# GarderOpa.net
KiCad netlist of a schematic drawn in EAGLE
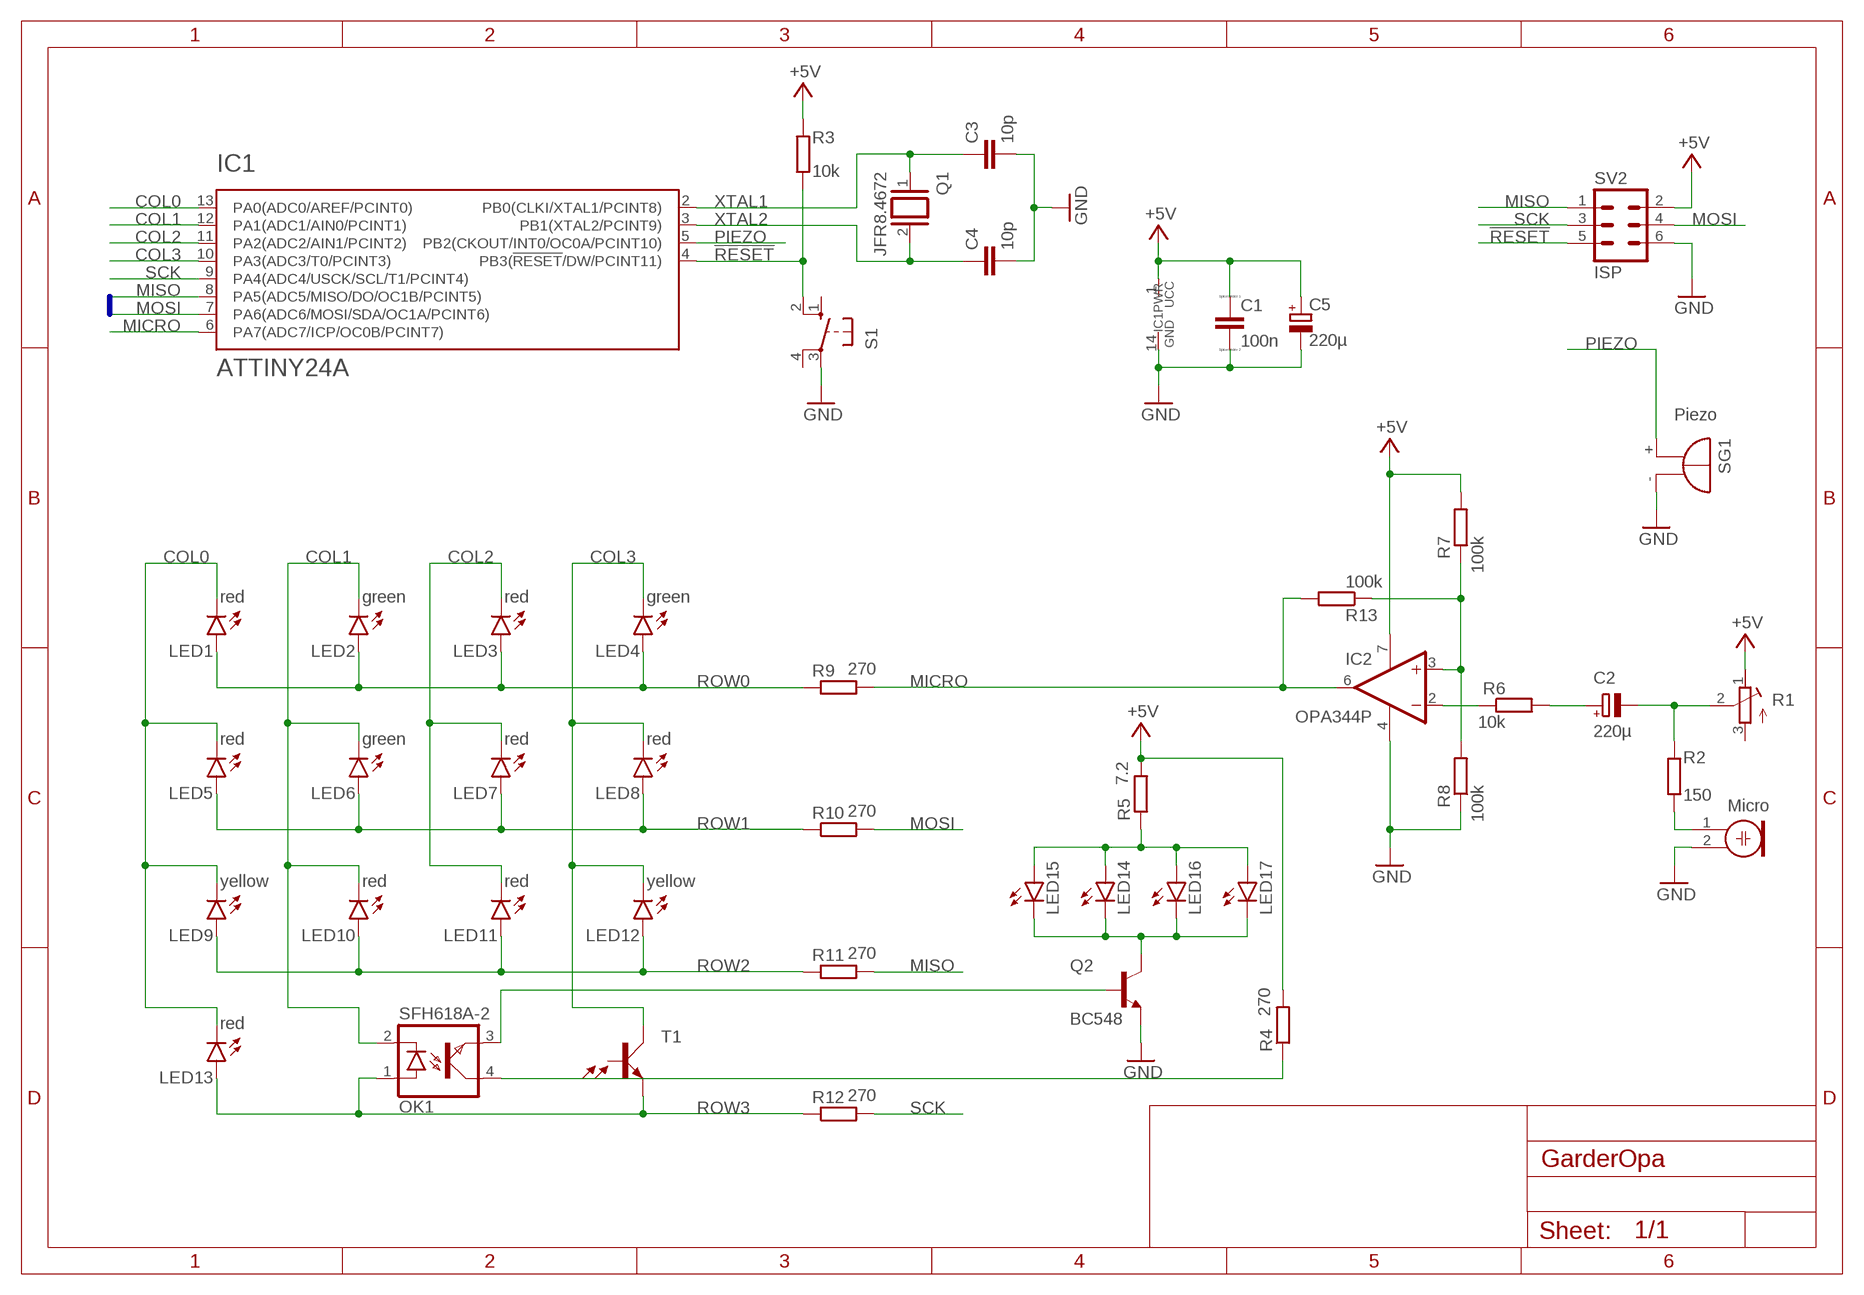
[diagram p0: schematic, sheet 1]

(export (version "E")
  (design (tool "Eeschema 10.0.6"))
  (components
    (comp (ref "C1")
      (value "100n")
      (footprint "eagle-import:C0603")
      (libsource (lib "eagle-import") (part "CC0603"))
    )
    (comp (ref "C2")
      (value "220µ")
      (footprint "eagle-import:E2-4")
      (libsource (lib "eagle-import") (part "CPOL-EUE2-4"))
    )
    (comp (ref "C3")
      (value "10p")
      (footprint "eagle-import:C025-024X044")
      (libsource (lib "eagle-import") (part "C-EU025-024X044"))
    )
    (comp (ref "C4")
      (value "10p")
      (footprint "eagle-import:C025-024X044")
      (libsource (lib "eagle-import") (part "C-EU025-024X044"))
    )
    (comp (ref "C5")
      (value "220µ")
      (footprint "eagle-import:E2-4")
      (libsource (lib "eagle-import") (part "CPOL-EUE2-4"))
    )
    (comp (ref "IC1")
      (value "ATTINY24A")
      (footprint "eagle-import:DIL14")
      (libsource (lib "eagle-import") (part "ATTINY24/44/84-PU"))
    )
    (comp (ref "IC2")
      (value "OPA344P")
      (footprint "eagle-import:DIL08")
      (libsource (lib "eagle-import") (part "OPAP344"))
    )
    (comp (ref "LED1")
      (value "red")
      (footprint "eagle-import:LED3MM")
      (libsource (lib "eagle-import") (part "LED3MM"))
    )
    (comp (ref "LED2")
      (value "green")
      (footprint "eagle-import:LED3MM")
      (libsource (lib "eagle-import") (part "LED3MM"))
    )
    (comp (ref "LED3")
      (value "red")
      (footprint "eagle-import:LED3MM")
      (libsource (lib "eagle-import") (part "LED3MM"))
    )
    (comp (ref "LED4")
      (value "green")
      (footprint "eagle-import:LED3MM")
      (libsource (lib "eagle-import") (part "LED3MM"))
    )
    (comp (ref "LED5")
      (value "red")
      (footprint "eagle-import:LED3MM")
      (libsource (lib "eagle-import") (part "LED3MM"))
    )
    (comp (ref "LED6")
      (value "green")
      (footprint "eagle-import:LED3MM")
      (libsource (lib "eagle-import") (part "LED3MM"))
    )
    (comp (ref "LED7")
      (value "red")
      (footprint "eagle-import:LED3MM")
      (libsource (lib "eagle-import") (part "LED3MM"))
    )
    (comp (ref "LED8")
      (value "red")
      (footprint "eagle-import:LED3MM")
      (libsource (lib "eagle-import") (part "LED3MM"))
    )
    (comp (ref "LED9")
      (value "yellow")
      (footprint "eagle-import:LED3MM")
      (libsource (lib "eagle-import") (part "LED3MM"))
    )
    (comp (ref "LED10")
      (value "red")
      (footprint "eagle-import:LED3MM")
      (libsource (lib "eagle-import") (part "LED3MM"))
    )
    (comp (ref "LED11")
      (value "red")
      (footprint "eagle-import:LED3MM")
      (libsource (lib "eagle-import") (part "LED3MM"))
    )
    (comp (ref "LED12")
      (value "yellow")
      (footprint "eagle-import:LED3MM")
      (libsource (lib "eagle-import") (part "LED3MM"))
    )
    (comp (ref "LED13")
      (value "red")
      (footprint "eagle-import:LED3MM")
      (libsource (lib "eagle-import") (part "LED3MM"))
    )
    (comp (ref "LED14")
      (value "LED5MM")
      (footprint "eagle-import:LED5MM")
      (libsource (lib "eagle-import") (part "LED5MM"))
    )
    (comp (ref "LED15")
      (value "LED5MM")
      (footprint "eagle-import:LED5MM")
      (libsource (lib "eagle-import") (part "LED5MM"))
    )
    (comp (ref "LED16")
      (value "LED5MM")
      (footprint "eagle-import:LED5MM")
      (libsource (lib "eagle-import") (part "LED5MM"))
    )
    (comp (ref "LED17")
      (value "LED5MM")
      (footprint "eagle-import:LED5MM")
      (libsource (lib "eagle-import") (part "LED5MM"))
    )
    (comp (ref "M1")
      (value "Micro")
      (footprint "eagle-import:WM-61B")
      (fields (field (name "MIC") "Micro"))
      (libsource (lib "eagle-import") (part "ELECTRET_MICROPHON-WM-61B"))
    )
    (comp (ref "OK1")
      (value "SFH618A-2")
      (footprint "eagle-import:DIP4")
      (fields (field (name "MF") "VISHAY/TELEFUNKEN"))
      (libsource (lib "eagle-import") (part "SFH618?A-2"))
    )
    (comp (ref "Q1")
      (value "JFR8.4672")
      (footprint "eagle-import:QS")
      (libsource (lib "eagle-import") (part "XTAL/S"))
    )
    (comp (ref "Q2")
      (value "BC548")
      (footprint "eagle-import:TO92-EBC")
      (libsource (lib "eagle-import") (part "BC548"))
    )
    (comp (ref "R1")
      (value "R-TRIMM43P")
      (footprint "eagle-import:RTRIM43P")
      (libsource (lib "eagle-import") (part "R-TRIMM43P"))
    )
    (comp (ref "R2")
      (value "150")
      (footprint "eagle-import:0204_7")
      (libsource (lib "eagle-import") (part "rcl_334_R-EU_0204/7"))
    )
    (comp (ref "R3")
      (value "10k")
      (footprint "eagle-import:R0603")
      (libsource (lib "eagle-import") (part "R-EU_R0603"))
    )
    (comp (ref "R4")
      (value "270")
      (footprint "eagle-import:R0603")
      (libsource (lib "eagle-import") (part "R-EU_R0603"))
    )
    (comp (ref "R5")
      (value "7.2")
      (footprint "eagle-import:R0603")
      (libsource (lib "eagle-import") (part "R-EU_R0603"))
    )
    (comp (ref "R6")
      (value "10k")
      (footprint "eagle-import:0204_7")
      (libsource (lib "eagle-import") (part "rcl_334_R-EU_0204/7"))
    )
    (comp (ref "R7")
      (value "100k")
      (footprint "eagle-import:0204_7")
      (libsource (lib "eagle-import") (part "rcl_334_R-EU_0204/7"))
    )
    (comp (ref "R8")
      (value "100k")
      (footprint "eagle-import:0204_7")
      (libsource (lib "eagle-import") (part "rcl_334_R-EU_0204/7"))
    )
    (comp (ref "R9")
      (value "270")
      (footprint "eagle-import:R0603")
      (libsource (lib "eagle-import") (part "R-EU_R0603"))
    )
    (comp (ref "R10")
      (value "270")
      (footprint "eagle-import:R0603")
      (libsource (lib "eagle-import") (part "R-EU_R0603"))
    )
    (comp (ref "R11")
      (value "270")
      (footprint "eagle-import:R0603")
      (libsource (lib "eagle-import") (part "R-EU_R0603"))
    )
    (comp (ref "R12")
      (value "270")
      (footprint "eagle-import:R0603")
      (libsource (lib "eagle-import") (part "R-EU_R0603"))
    )
    (comp (ref "R13")
      (value "100k")
      (footprint "eagle-import:0204_7")
      (libsource (lib "eagle-import") (part "rcl_334_R-EU_0204/7"))
    )
    (comp (ref "S1")
      (value "10-XX")
      (footprint "eagle-import:B3F-10XX")
      (fields (field (name "MPN") "B3F-1000"))
      (libsource (lib "eagle-import") (part "10-XX"))
    )
    (comp (ref "SG1")
      (value "Piezo")
      (footprint "eagle-import:EB2505")
      (libsource (lib "eagle-import") (part "EB2505"))
    )
    (comp (ref "SV2")
      (value "ISP")
      (footprint "eagle-import:MA03-2")
      (libsource (lib "eagle-import") (part "MA03-2"))
    )
    (comp (ref "T1")
      (value "SFH303")
      (footprint "eagle-import:SFH303")
      (libsource (lib "eagle-import") (part "SFH303"))
    )
  )
  (nets
    (net (code "1") (name "+5V") (class "Default")
      (node (ref "C1") (pin "1") (pinfunction "1_1") (pintype "passive"))
      (node (ref "C5") (pin "+") (pinfunction "+_+") (pintype "passive"))
      (node (ref "IC1") (pin "1") (pinfunction "UCC_1") (pintype "power_in"))
      (node (ref "IC2") (pin "7") (pinfunction "V+_7") (pintype "power_in"))
      (node (ref "R1") (pin "1") (pinfunction "E_1") (pintype "passive"))
      (node (ref "R3") (pin "2") (pinfunction "2_2") (pintype "passive"))
      (node (ref "R4") (pin "2") (pinfunction "2_2") (pintype "passive"))
      (node (ref "R5") (pin "2") (pinfunction "2_2") (pintype "passive"))
      (node (ref "R7") (pin "2") (pinfunction "2_2") (pintype "passive"))
      (node (ref "SV2") (pin "2") (pinfunction "2_2") (pintype "passive"))
    )
    (net (code "2") (name "/COL0") (class "Default")
      (node (ref "IC1") (pin "13") (pinfunction "PA0(ADC0/AREF/PCINT0)_13") (pintype "bidirectional"))
      (node (ref "LED1") (pin "K") (pinfunction "C_K") (pintype "passive"))
      (node (ref "LED13") (pin "K") (pinfunction "C_K") (pintype "passive"))
      (node (ref "LED5") (pin "K") (pinfunction "C_K") (pintype "passive"))
      (node (ref "LED9") (pin "K") (pinfunction "C_K") (pintype "passive"))
    )
    (net (code "3") (name "/COL1") (class "Default")
      (node (ref "IC1") (pin "12") (pinfunction "PA1(ADC1/AIN0/PCINT1)_12") (pintype "bidirectional"))
      (node (ref "LED10") (pin "K") (pinfunction "C_K") (pintype "passive"))
      (node (ref "LED2") (pin "K") (pinfunction "C_K") (pintype "passive"))
      (node (ref "LED6") (pin "K") (pinfunction "C_K") (pintype "passive"))
      (node (ref "OK1") (pin "2") (pinfunction "C_2") (pintype "passive"))
    )
    (net (code "4") (name "/COL2") (class "Default")
      (node (ref "IC1") (pin "11") (pinfunction "PA2(ADC2/AIN1/PCINT2)_11") (pintype "bidirectional"))
      (node (ref "LED11") (pin "K") (pinfunction "C_K") (pintype "passive"))
      (node (ref "LED3") (pin "K") (pinfunction "C_K") (pintype "passive"))
      (node (ref "LED7") (pin "K") (pinfunction "C_K") (pintype "passive"))
    )
    (net (code "5") (name "/COL3") (class "Default")
      (node (ref "IC1") (pin "10") (pinfunction "PA3(ADC3/T0/PCINT3)_10") (pintype "bidirectional"))
      (node (ref "LED12") (pin "K") (pinfunction "C_K") (pintype "passive"))
      (node (ref "LED4") (pin "K") (pinfunction "C_K") (pintype "passive"))
      (node (ref "LED8") (pin "K") (pinfunction "C_K") (pintype "passive"))
      (node (ref "T1") (pin "2") (pinfunction "C_2") (pintype "passive"))
    )
    (net (code "6") (name "/MICRO") (class "Default")
      (node (ref "IC1") (pin "6") (pinfunction "PA7(ADC7/ICP/OC0B/PCINT7)_6") (pintype "bidirectional"))
      (node (ref "IC2") (pin "6") (pinfunction "OUT_6") (pintype "output"))
      (node (ref "R13") (pin "2") (pinfunction "2_2") (pintype "passive"))
      (node (ref "R9") (pin "2") (pinfunction "2_2") (pintype "passive"))
    )
    (net (code "7") (name "/MISO") (class "Default")
      (node (ref "IC1") (pin "8") (pinfunction "PA5(ADC5/MISO/DO/OC1B/PCINT5)_8") (pintype "bidirectional"))
      (node (ref "R11") (pin "2") (pinfunction "2_2") (pintype "passive"))
      (node (ref "SV2") (pin "1") (pinfunction "1_1") (pintype "passive"))
    )
    (net (code "8") (name "/MOSI") (class "Default")
      (node (ref "IC1") (pin "7") (pinfunction "PA6(ADC6/MOSI/SDA/OC1A/PCINT6)_7") (pintype "bidirectional"))
      (node (ref "R10") (pin "2") (pinfunction "2_2") (pintype "passive"))
      (node (ref "SV2") (pin "4") (pinfunction "4_4") (pintype "passive"))
    )
    (net (code "9") (name "/PIEZO") (class "Default")
      (node (ref "IC1") (pin "5") (pinfunction "PB2(CKOUT/INT0/OC0A/PCINT10)_5") (pintype "bidirectional"))
      (node (ref "SG1") (pin "+") (pinfunction "+_+") (pintype "passive"))
    )
    (net (code "10") (name "/ROW0") (class "Default")
      (node (ref "LED1") (pin "A") (pinfunction "A_A") (pintype "passive"))
      (node (ref "LED2") (pin "A") (pinfunction "A_A") (pintype "passive"))
      (node (ref "LED3") (pin "A") (pinfunction "A_A") (pintype "passive"))
      (node (ref "LED4") (pin "A") (pinfunction "A_A") (pintype "passive"))
      (node (ref "R9") (pin "1") (pinfunction "1_1") (pintype "passive"))
    )
    (net (code "11") (name "/ROW1") (class "Default")
      (node (ref "LED5") (pin "A") (pinfunction "A_A") (pintype "passive"))
      (node (ref "LED6") (pin "A") (pinfunction "A_A") (pintype "passive"))
      (node (ref "LED7") (pin "A") (pinfunction "A_A") (pintype "passive"))
      (node (ref "LED8") (pin "A") (pinfunction "A_A") (pintype "passive"))
      (node (ref "R10") (pin "1") (pinfunction "1_1") (pintype "passive"))
    )
    (net (code "12") (name "/ROW2") (class "Default")
      (node (ref "LED10") (pin "A") (pinfunction "A_A") (pintype "passive"))
      (node (ref "LED11") (pin "A") (pinfunction "A_A") (pintype "passive"))
      (node (ref "LED12") (pin "A") (pinfunction "A_A") (pintype "passive"))
      (node (ref "LED9") (pin "A") (pinfunction "A_A") (pintype "passive"))
      (node (ref "R11") (pin "1") (pinfunction "1_1") (pintype "passive"))
    )
    (net (code "13") (name "/ROW3") (class "Default")
      (node (ref "LED13") (pin "A") (pinfunction "A_A") (pintype "passive"))
      (node (ref "OK1") (pin "1") (pinfunction "A_1") (pintype "passive"))
      (node (ref "R12") (pin "1") (pinfunction "1_1") (pintype "passive"))
      (node (ref "T1") (pin "1") (pinfunction "E_1") (pintype "passive"))
    )
    (net (code "14") (name "/SCK") (class "Default")
      (node (ref "IC1") (pin "9") (pinfunction "PA4(ADC4/USCK/SCL/T1/PCINT4)_9") (pintype "bidirectional"))
      (node (ref "R12") (pin "2") (pinfunction "2_2") (pintype "passive"))
      (node (ref "SV2") (pin "3") (pinfunction "3_3") (pintype "passive"))
    )
    (net (code "15") (name "/XTAL1") (class "Default")
      (node (ref "C3") (pin "1") (pinfunction "1_1") (pintype "passive"))
      (node (ref "IC1") (pin "2") (pinfunction "PB0(CLKI/XTAL1/PCINT8)_2") (pintype "bidirectional"))
      (node (ref "Q1") (pin "1") (pinfunction "1_1") (pintype "passive"))
    )
    (net (code "16") (name "/XTAL2") (class "Default")
      (node (ref "C4") (pin "1") (pinfunction "1_1") (pintype "passive"))
      (node (ref "IC1") (pin "3") (pinfunction "PB1(XTAL2/PCINT9)_3") (pintype "bidirectional"))
      (node (ref "Q1") (pin "2") (pinfunction "2_2") (pintype "passive"))
    )
    (net (code "17") (name "/~{RESET}") (class "Default")
      (node (ref "IC1") (pin "4") (pinfunction "PB3(~{RESET}/DW/PCINT11)_4") (pintype "bidirectional"))
      (node (ref "R3") (pin "1") (pinfunction "1_1") (pintype "passive"))
      (node (ref "S1") (pin "2") (pinfunction "S1_2") (pintype "passive"))
      (node (ref "SV2") (pin "5") (pinfunction "5_5") (pintype "passive"))
    )
    (net (code "18") (name "GND") (class "Default")
      (node (ref "C1") (pin "2") (pinfunction "2_2") (pintype "passive"))
      (node (ref "C3") (pin "2") (pinfunction "2_2") (pintype "passive"))
      (node (ref "C4") (pin "2") (pinfunction "2_2") (pintype "passive"))
      (node (ref "C5") (pin "-") (pinfunction "-_-") (pintype "passive"))
      (node (ref "IC1") (pin "14") (pinfunction "GND_14") (pintype "power_in"))
      (node (ref "IC2") (pin "4") (pinfunction "V-_4") (pintype "power_in"))
      (node (ref "M1") (pin "2") (pinfunction "2_2") (pintype "passive"))
      (node (ref "Q2") (pin "E") (pinfunction "E_E") (pintype "passive"))
      (node (ref "R8") (pin "1") (pinfunction "1_1") (pintype "passive"))
      (node (ref "S1") (pin "3") (pinfunction "P_3") (pintype "passive"))
      (node (ref "SG1") (pin "-") (pinfunction "-_-") (pintype "passive"))
      (node (ref "SV2") (pin "6") (pinfunction "6_6") (pintype "passive"))
    )
    (net (code "19") (name "Net-(C2-Pad+)") (class "Default")
      (node (ref "C2") (pin "+") (pinfunction "+_+") (pintype "passive"))
      (node (ref "R6") (pin "2") (pinfunction "2_2") (pintype "passive"))
    )
    (net (code "20") (name "Net-(IC2-+IN)") (class "Default")
      (node (ref "IC2") (pin "3") (pinfunction "+IN_3") (pintype "input"))
      (node (ref "R13") (pin "1") (pinfunction "1_1") (pintype "passive"))
      (node (ref "R7") (pin "1") (pinfunction "1_1") (pintype "passive"))
      (node (ref "R8") (pin "2") (pinfunction "2_2") (pintype "passive"))
    )
    (net (code "21") (name "Net-(IC2--IN)") (class "Default")
      (node (ref "IC2") (pin "2") (pinfunction "-IN_2") (pintype "input"))
      (node (ref "R6") (pin "1") (pinfunction "1_1") (pintype "passive"))
    )
    (net (code "22") (name "Net-(LED14-C)") (class "Default")
      (node (ref "LED14") (pin "K") (pinfunction "C_K") (pintype "passive"))
      (node (ref "LED15") (pin "K") (pinfunction "C_K") (pintype "passive"))
      (node (ref "LED16") (pin "K") (pinfunction "C_K") (pintype "passive"))
      (node (ref "LED17") (pin "K") (pinfunction "C_K") (pintype "passive"))
      (node (ref "Q2") (pin "C") (pinfunction "C_C") (pintype "passive"))
    )
    (net (code "23") (name "Net-(LED14-PadA)") (class "Default")
      (node (ref "LED14") (pin "A") (pinfunction "A_A") (pintype "passive"))
      (node (ref "LED15") (pin "A") (pinfunction "A_A") (pintype "passive"))
      (node (ref "LED16") (pin "A") (pinfunction "A_A") (pintype "passive"))
      (node (ref "LED17") (pin "A") (pinfunction "A_A") (pintype "passive"))
      (node (ref "R5") (pin "1") (pinfunction "1_1") (pintype "passive"))
    )
    (net (code "24") (name "Net-(M1-Pad1)") (class "Default")
      (node (ref "M1") (pin "1") (pinfunction "1_1") (pintype "passive"))
      (node (ref "R2") (pin "2") (pinfunction "2_2") (pintype "passive"))
    )
    (net (code "25") (name "Net-(OK1-COL)") (class "Default")
      (node (ref "OK1") (pin "4") (pinfunction "COL_4") (pintype "passive"))
      (node (ref "R4") (pin "1") (pinfunction "1_1") (pintype "passive"))
    )
    (net (code "26") (name "Net-(OK1-EMIT)") (class "Default")
      (node (ref "OK1") (pin "3") (pinfunction "EMIT_3") (pintype "passive"))
      (node (ref "Q2") (pin "B") (pinfunction "B_B") (pintype "passive"))
    )
    (net (code "27") (name "Net-(R1-S)") (class "Default")
      (node (ref "C2") (pin "-") (pinfunction "-_-") (pintype "passive"))
      (node (ref "R1") (pin "2") (pinfunction "S_2") (pintype "passive"))
      (node (ref "R2") (pin "1") (pinfunction "1_1") (pintype "passive"))
    )
    (net (code "28") (name "unconnected-(R1-A-Pad3)") (class "Default")
      (node (ref "R1") (pin "3") (pinfunction "A_3") (pintype "passive"))
    )
    (net (code "29") (name "unconnected-(S1-P1-Pad4)") (class "Default")
      (node (ref "S1") (pin "4") (pinfunction "P1_4") (pintype "passive"))
    )
    (net (code "30") (name "unconnected-(S1-S-Pad1)") (class "Default")
      (node (ref "S1") (pin "1") (pinfunction "S_1") (pintype "passive"))
    )
    (net (code "31") (name "unconnected-(T1-B-Pad3)") (class "Default")
      (node (ref "T1") (pin "3") (pinfunction "B_3") (pintype "passive"))
    )
  )
)
